# Rx_BEC_V2-1.net
KiCad netlist of a schematic drawn in EAGLE
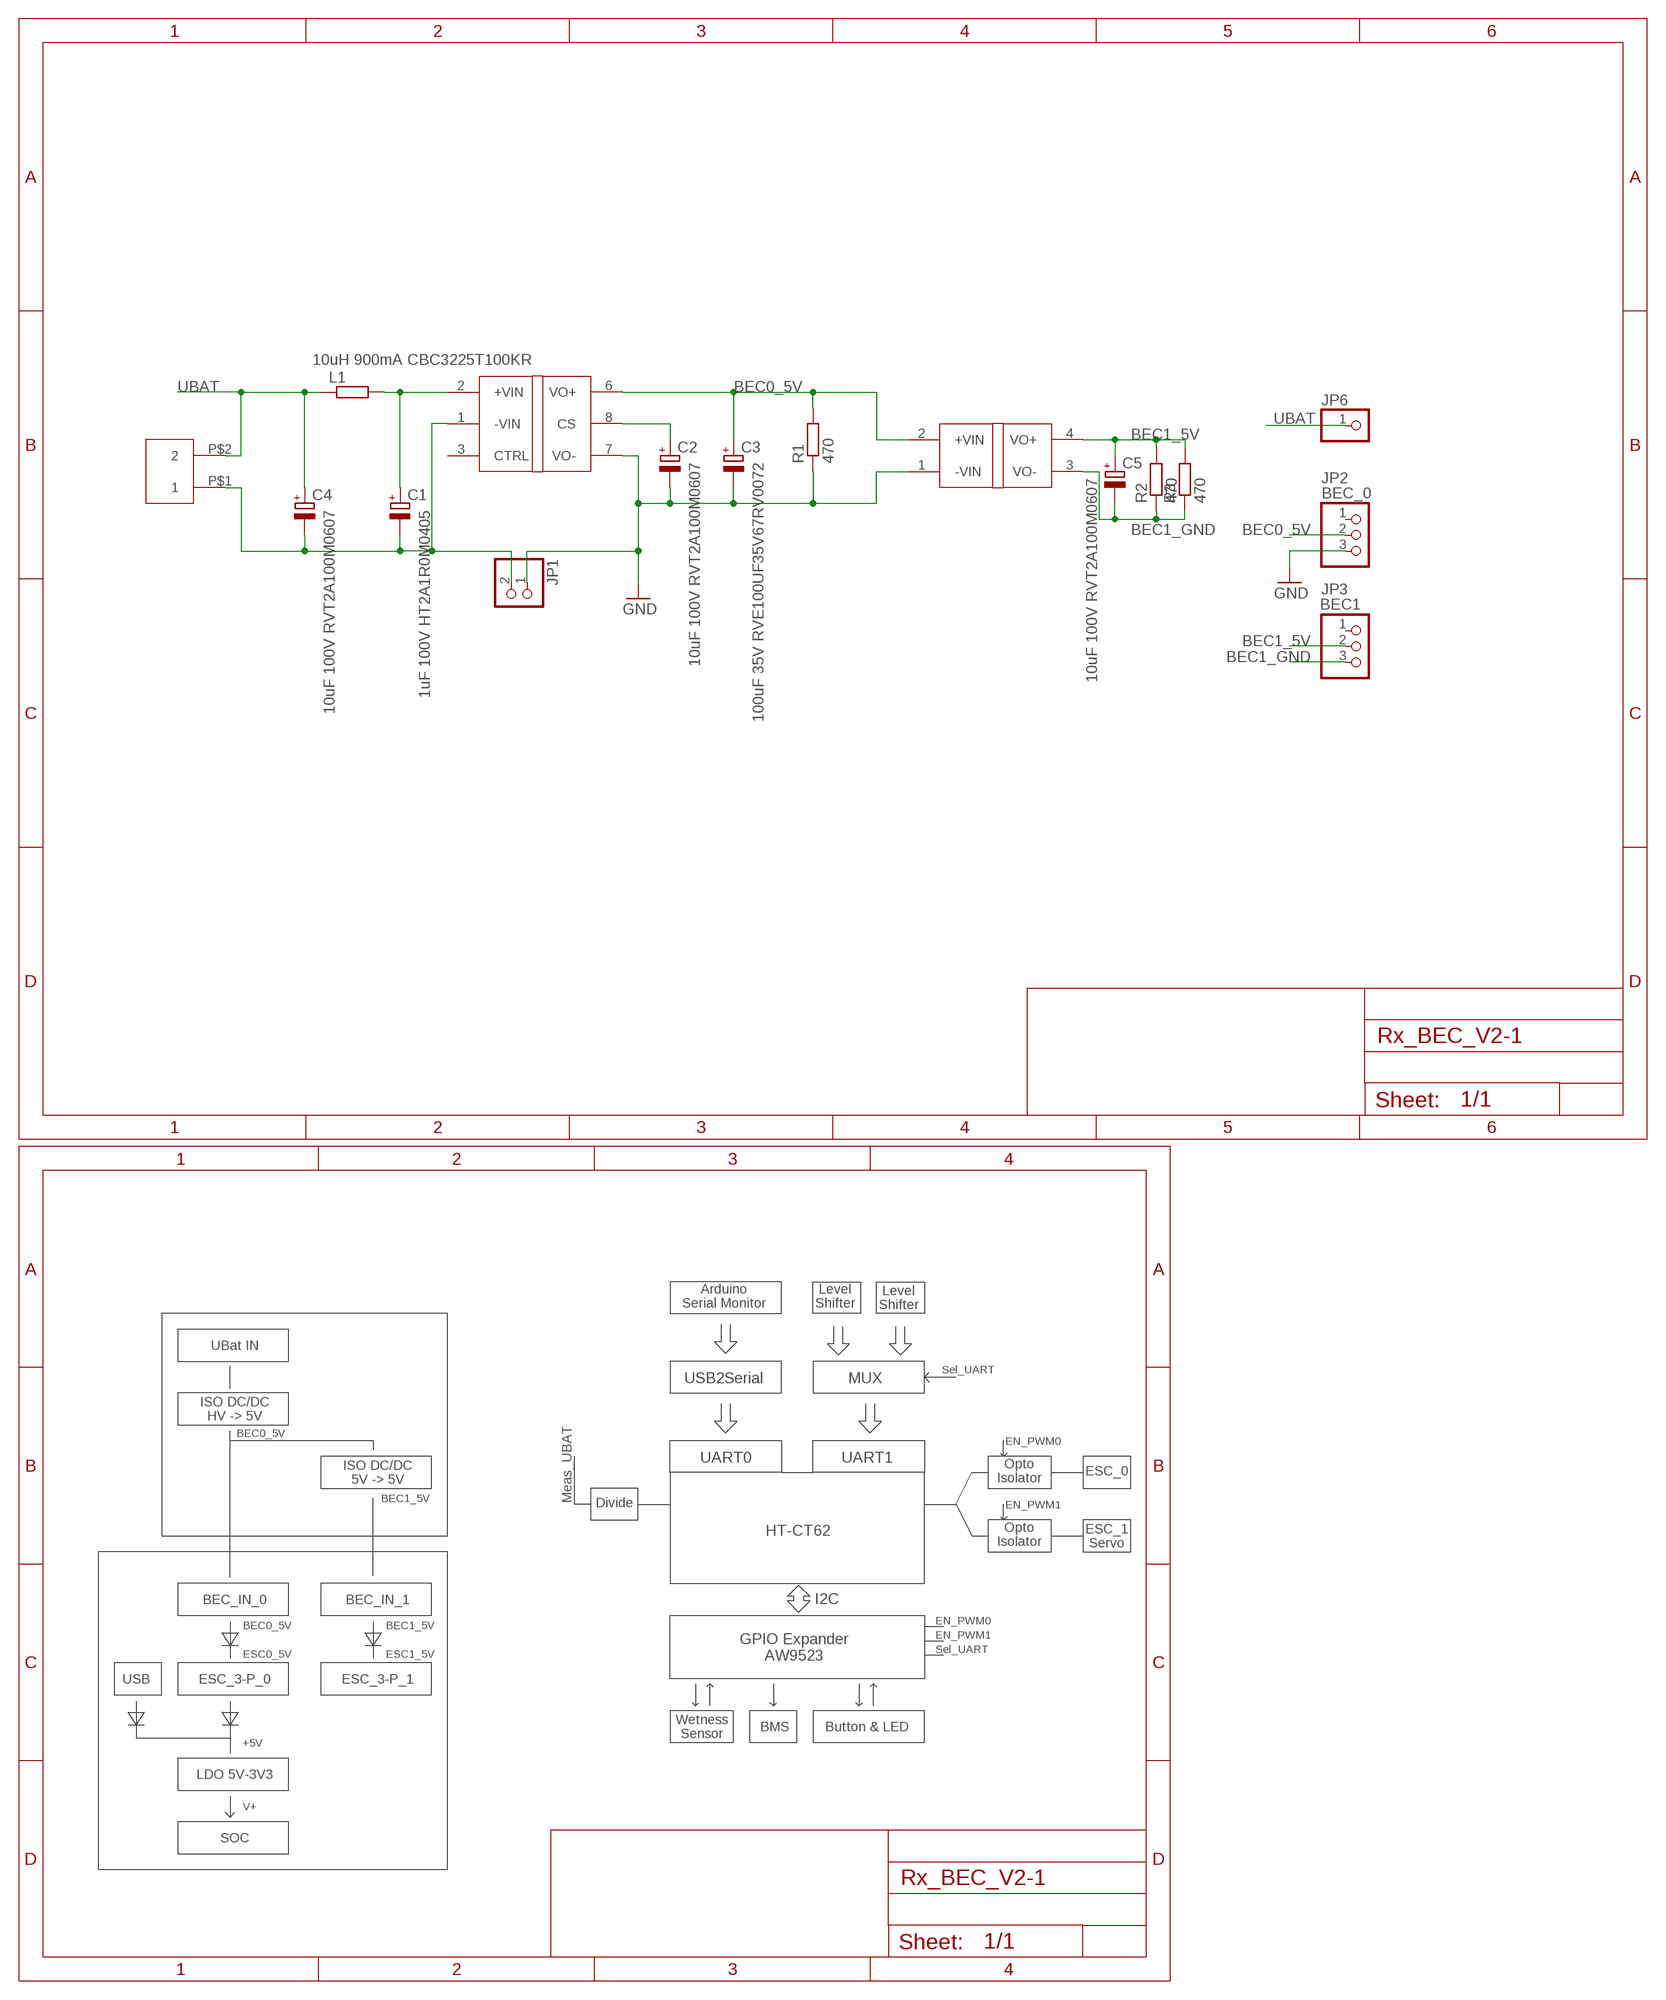
[diagram p0: schematic, sheet 1]

(export (version "E")
  (design (tool "Eeschema 10.0.6"))
  (components
    (comp (ref "C1")
      (value "1uF 100V HT2A1R0M0405")
      (footprint "eagle-import:153CLV-0405")
      (libsource (lib "eagle-import") (part "CPOL-EU153CLV-0405"))
    )
    (comp (ref "C2")
      (value "10uF 100V RVT2A100M0607")
      (footprint "eagle-import:153CLV-0605")
      (libsource (lib "eagle-import") (part "CPOL-EU153CLV-0605"))
    )
    (comp (ref "C3")
      (value "100uF 35V RVE100UF35V67RV0072")
      (footprint "eagle-import:153CLV-0605")
      (libsource (lib "eagle-import") (part "CPOL-EU153CLV-0605"))
    )
    (comp (ref "C4")
      (value "10uF 100V RVT2A100M0607")
      (footprint "eagle-import:153CLV-0605")
      (libsource (lib "eagle-import") (part "CPOL-EU153CLV-0605"))
    )
    (comp (ref "C5")
      (value "10uF 100V RVT2A100M0607")
      (footprint "eagle-import:153CLV-0605")
      (libsource (lib "eagle-import") (part "CPOL-EU153CLV-0605"))
    )
    (comp (ref "JP1")
      (value "PINHD-1X2")
      (footprint "eagle-import:1X02")
      (libsource (lib "eagle-import") (part "PINHD-1X2"))
    )
    (comp (ref "JP2")
      (value "BEC_0")
      (footprint "eagle-import:1X03")
      (libsource (lib "eagle-import") (part "PINHD-1X3"))
    )
    (comp (ref "JP3")
      (value "BEC1")
      (footprint "eagle-import:1X03")
      (libsource (lib "eagle-import") (part "PINHD-1X3"))
    )
    (comp (ref "JP6")
      (value "PINHD-1X1")
      (footprint "eagle-import:1X01")
      (libsource (lib "eagle-import") (part "PINHD-1X1"))
    )
    (comp (ref "L1")
      (value "10uH 900mA CBC3225T100KR")
      (footprint "eagle-import:R1210")
      (libsource (lib "eagle-import") (part "R-EU_R1210"))
    )
    (comp (ref "R1")
      (value "470")
      (footprint "eagle-import:R0805")
      (libsource (lib "eagle-import") (part "R-EU_R0805"))
    )
    (comp (ref "R2")
      (value "470")
      (footprint "eagle-import:R0805")
      (libsource (lib "eagle-import") (part "R-EU_R0805"))
    )
    (comp (ref "R3")
      (value "470")
      (footprint "eagle-import:R0805")
      (libsource (lib "eagle-import") (part "R-EU_R0805"))
    )
    (comp (ref "U$1")
      (value "WJ126V-5.0-2P")
      (footprint "eagle-import:WJ126V-5.0-2P")
      (libsource (lib "eagle-import") (part "WJ126V-5.0-2P"))
    )
    (comp (ref "U$2")
      (value "B0505S-1WR3")
      (footprint "eagle-import:B0505S-1WR3")
      (libsource (lib "eagle-import") (part "B0505S-1WR3"))
    )
    (comp (ref "U$3")
      (value "URB4805S-3WR3")
      (footprint "eagle-import:URB4805S-3WR3")
      (libsource (lib "eagle-import") (part "URB4805S-3WR3"))
    )
  )
  (nets
    (net (code "1") (name "/BEC0_5V") (class "Default")
      (node (ref "C3") (pin "+") (pinfunction "+_+") (pintype "passive"))
      (node (ref "JP2") (pin "2") (pinfunction "2_2") (pintype "passive"))
      (node (ref "R1") (pin "2") (pinfunction "2_2") (pintype "passive"))
      (node (ref "U$2") (pin "2") (pinfunction "+VIN_2") (pintype "bidirectional"))
      (node (ref "U$3") (pin "6") (pinfunction "VO+_6") (pintype "bidirectional"))
    )
    (net (code "2") (name "/BEC1_5V") (class "Default")
      (node (ref "C5") (pin "+") (pinfunction "+_+") (pintype "passive"))
      (node (ref "JP3") (pin "2") (pinfunction "2_2") (pintype "passive"))
      (node (ref "R2") (pin "2") (pinfunction "2_2") (pintype "passive"))
      (node (ref "R3") (pin "2") (pinfunction "2_2") (pintype "passive"))
      (node (ref "U$2") (pin "4") (pinfunction "VO+_4") (pintype "bidirectional"))
    )
    (net (code "3") (name "/BEC1_GND") (class "Default")
      (node (ref "C5") (pin "-") (pinfunction "-_-") (pintype "passive"))
      (node (ref "JP3") (pin "3") (pinfunction "3_3") (pintype "passive"))
      (node (ref "R2") (pin "1") (pinfunction "1_1") (pintype "passive"))
      (node (ref "R3") (pin "1") (pinfunction "1_1") (pintype "passive"))
      (node (ref "U$2") (pin "3") (pinfunction "VO-_3") (pintype "bidirectional"))
    )
    (net (code "4") (name "/UBAT") (class "Default")
      (node (ref "C4") (pin "+") (pinfunction "+_+") (pintype "passive"))
      (node (ref "JP6") (pin "1") (pinfunction "1_1") (pintype "passive"))
      (node (ref "L1") (pin "1") (pinfunction "1_1") (pintype "passive"))
      (node (ref "U$1") (pin "P$2") (pinfunction "2_P$2") (pintype "bidirectional"))
    )
    (net (code "5") (name "GND") (class "Default")
      (node (ref "C2") (pin "-") (pinfunction "-_-") (pintype "passive"))
      (node (ref "C3") (pin "-") (pinfunction "-_-") (pintype "passive"))
      (node (ref "JP1") (pin "1") (pinfunction "1_1") (pintype "passive"))
      (node (ref "JP2") (pin "3") (pinfunction "3_3") (pintype "passive"))
      (node (ref "R1") (pin "1") (pinfunction "1_1") (pintype "passive"))
      (node (ref "U$2") (pin "1") (pinfunction "-VIN_1") (pintype "bidirectional"))
      (node (ref "U$3") (pin "7") (pinfunction "VO-_7") (pintype "bidirectional"))
    )
    (net (code "6") (name "Net-(U$1-1)") (class "Default")
      (node (ref "C1") (pin "-") (pinfunction "-_-") (pintype "passive"))
      (node (ref "C4") (pin "-") (pinfunction "-_-") (pintype "passive"))
      (node (ref "JP1") (pin "2") (pinfunction "2_2") (pintype "passive"))
      (node (ref "U$1") (pin "P$1") (pinfunction "1_P$1") (pintype "bidirectional"))
      (node (ref "U$3") (pin "1") (pinfunction "-VIN_1") (pintype "bidirectional"))
    )
    (net (code "7") (name "Net-(U$3-+VIN)") (class "Default")
      (node (ref "C1") (pin "+") (pinfunction "+_+") (pintype "passive"))
      (node (ref "L1") (pin "2") (pinfunction "2_2") (pintype "passive"))
      (node (ref "U$3") (pin "2") (pinfunction "+VIN_2") (pintype "bidirectional"))
    )
    (net (code "8") (name "Net-(U$3-CS)") (class "Default")
      (node (ref "C2") (pin "+") (pinfunction "+_+") (pintype "passive"))
      (node (ref "U$3") (pin "8") (pinfunction "CS_8") (pintype "bidirectional"))
    )
    (net (code "9") (name "unconnected-(JP2-Pad1)") (class "Default")
      (node (ref "JP2") (pin "1") (pinfunction "1_1") (pintype "passive"))
    )
    (net (code "10") (name "unconnected-(JP3-Pad1)") (class "Default")
      (node (ref "JP3") (pin "1") (pinfunction "1_1") (pintype "passive"))
    )
    (net (code "11") (name "unconnected-(U$3-CTRL-Pad3)") (class "Default")
      (node (ref "U$3") (pin "3") (pinfunction "CTRL_3") (pintype "bidirectional"))
    )
  )
)
